# Shema.net
KiCad netlist of a schematic drawn in Altium Designer
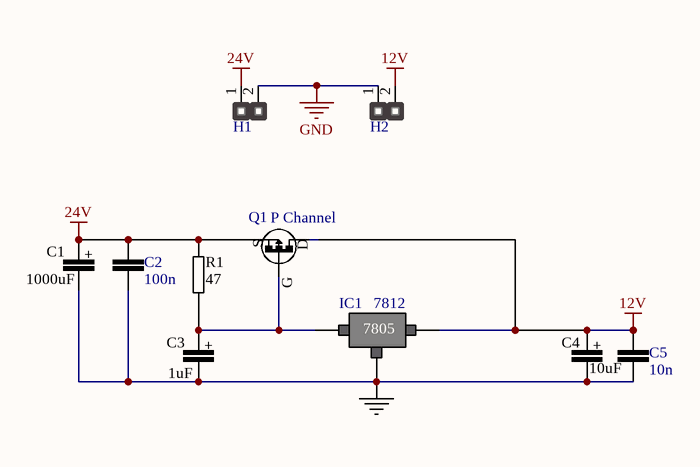
[diagram p0: Shema.SchDoc]

(export (version "E")
  (design (tool "Eeschema 10.0.6"))
  (components
    (comp (ref "C1")
      (value "1000uF")
      (footprint "C2(elektrolit)")
      (libsource (lib "KILEX LIB SCH") (part "C2"))
    )
    (comp (ref "C2") (value "100n") (footprint "C1(ceramic)") (libsource (lib "KILEX LIB SCH") (part "C1")))
    (comp (ref "C3") (value "1uF") (footprint "C1(ceramic)") (libsource (lib "KILEX LIB SCH") (part "C2")))
    (comp (ref "C4")
      (value "10uF")
      (footprint "C2(elektrolit)")
      (libsource (lib "KILEX LIB SCH") (part "C2"))
    )
    (comp (ref "C5") (value "10n") (footprint "C1(ceramic)") (libsource (lib "KILEX LIB SCH") (part "C1")))
    (comp (ref "H1")
      (value "Header1x2")
      (footprint "Header1x2")
      (libsource (lib "KILEX LIB SCH") (part "Header1x2"))
    )
    (comp (ref "H2")
      (value "Header1x2")
      (footprint "Header1x2")
      (libsource (lib "KILEX LIB SCH") (part "Header1x2"))
    )
    (comp (ref "IC1") (value "7812") (footprint "TO220") (libsource (lib "KILEX LIB SCH") (part "7805")))
    (comp (ref "Q1")
      (value "P Channel")
      (footprint "TO220")
      (libsource (lib "KILEX LIB SCH") (part "P-Channel MOSFET"))
    )
    (comp (ref "R1") (value "47") (footprint "R1(300milsa)") (libsource (lib "KILEX LIB SCH") (part "R1")))
  )
  (nets
    (net (code "1") (name "12V") (class "Default")
      (node (ref "C4") (pin "1") (pinfunction "1_1") (pintype "passive"))
      (node (ref "C5") (pin "1") (pinfunction "1_1") (pintype "passive"))
      (node (ref "H2") (pin "2") (pinfunction "2_2") (pintype "passive"))
      (node (ref "IC1") (pin "3") (pinfunction "3_3") (pintype "passive"))
      (node (ref "Q1") (pin "2") (pinfunction "2_2") (pintype "passive"))
    )
    (net (code "2") (name "24V") (class "Default")
      (node (ref "C1") (pin "1") (pinfunction "1_1") (pintype "passive"))
      (node (ref "C2") (pin "1") (pinfunction "1_1") (pintype "passive"))
      (node (ref "H1") (pin "1") (pinfunction "1_1") (pintype "passive"))
      (node (ref "Q1") (pin "3") (pinfunction "3_3") (pintype "passive"))
      (node (ref "R1") (pin "2") (pinfunction "2_2") (pintype "passive"))
    )
    (net (code "3") (name "GND") (class "Default")
      (node (ref "C1") (pin "2") (pinfunction "2_2") (pintype "passive"))
      (node (ref "C2") (pin "2") (pinfunction "2_2") (pintype "passive"))
      (node (ref "C3") (pin "2") (pinfunction "2_2") (pintype "passive"))
      (node (ref "C4") (pin "2") (pinfunction "2_2") (pintype "passive"))
      (node (ref "C5") (pin "2") (pinfunction "2_2") (pintype "passive"))
      (node (ref "H1") (pin "2") (pinfunction "2_2") (pintype "passive"))
      (node (ref "H2") (pin "1") (pinfunction "1_1") (pintype "passive"))
      (node (ref "IC1") (pin "2") (pinfunction "2_2") (pintype "passive"))
    )
    (net (code "4") (name "Net-(C3-Pad1)") (class "Default")
      (node (ref "C3") (pin "1") (pinfunction "1_1") (pintype "passive"))
      (node (ref "IC1") (pin "1") (pinfunction "1_1") (pintype "passive"))
      (node (ref "Q1") (pin "1") (pinfunction "1_1") (pintype "passive"))
      (node (ref "R1") (pin "1") (pinfunction "1_1") (pintype "passive"))
    )
  )
)
